# MRF49XA.net
KiCad netlist of a schematic drawn in EAGLE
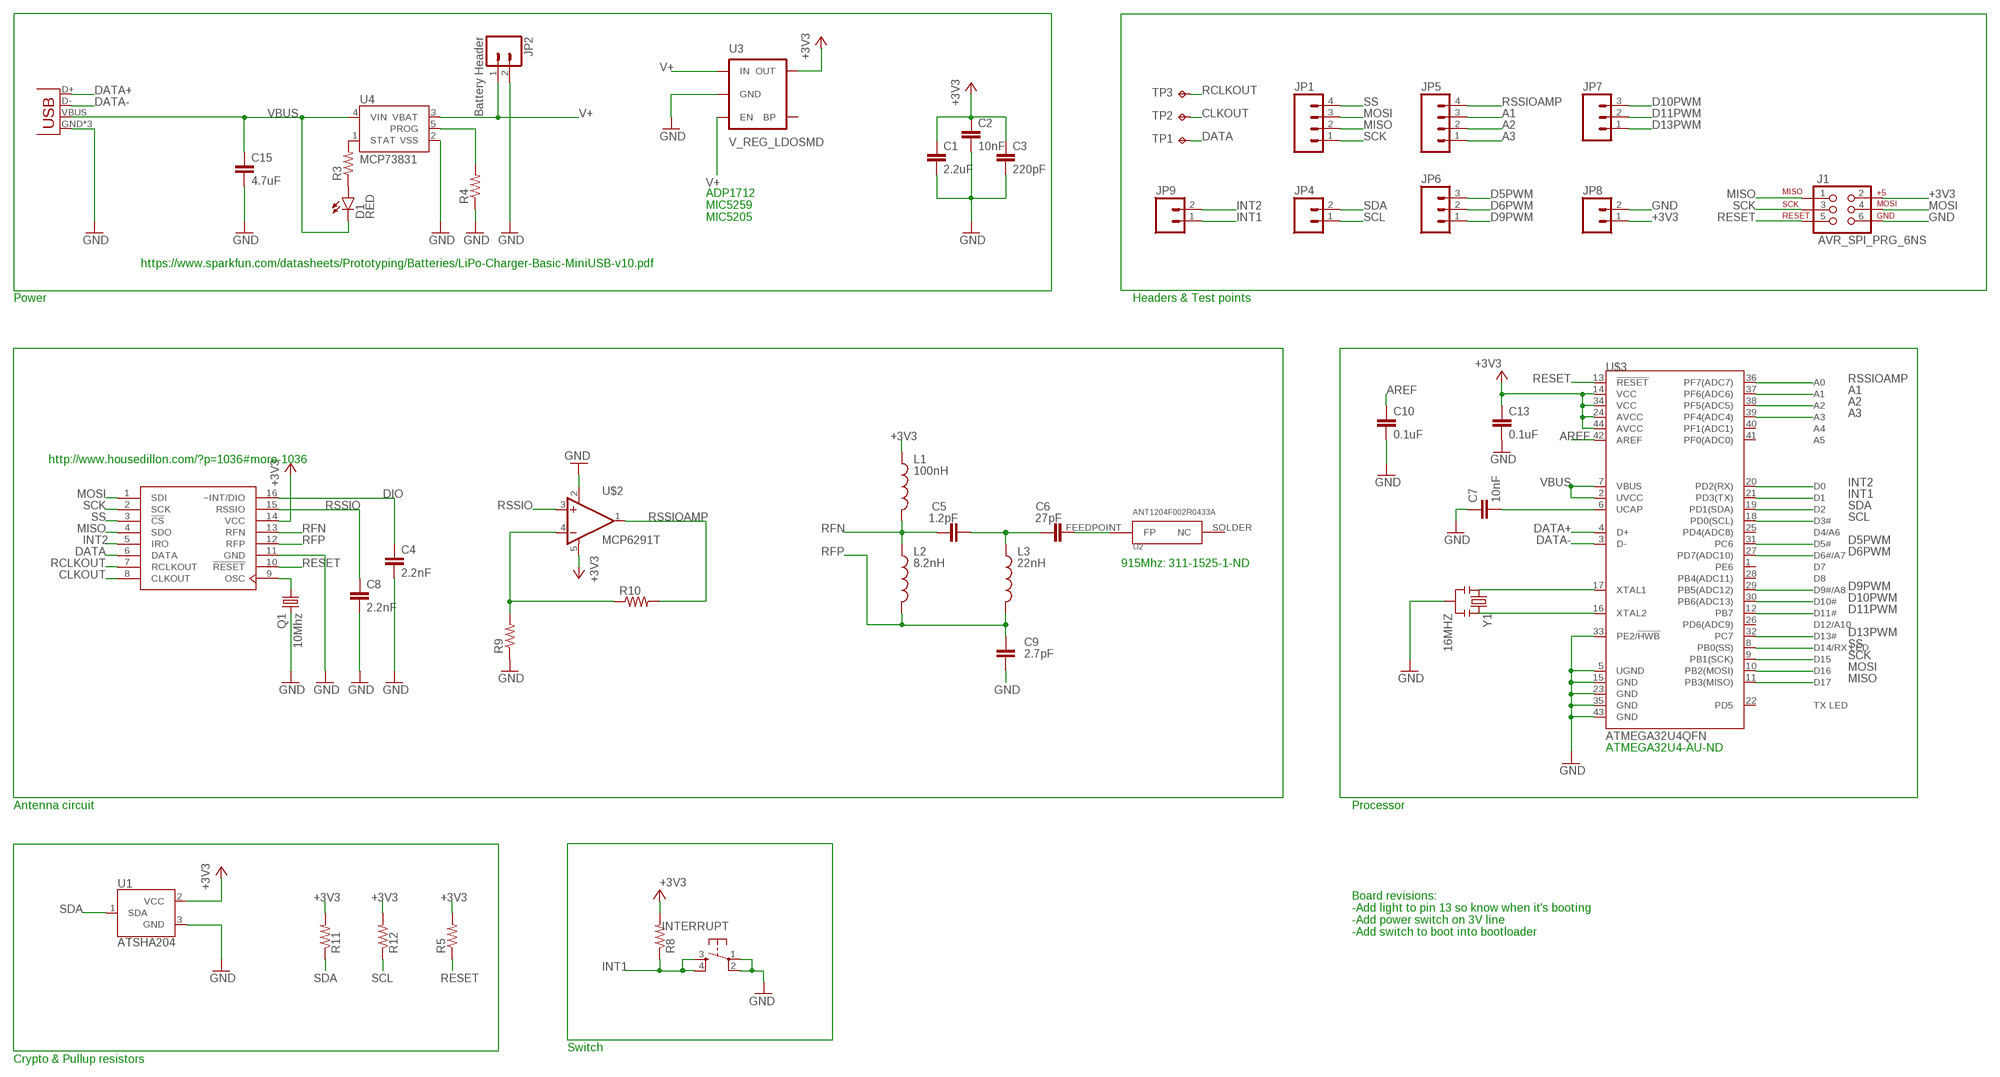
[diagram p0: schematic, sheet 1]

(export (version "E")
  (design (tool "Eeschema 10.0.6"))
  (components
    (comp (ref "C1")
      (value "2.2uF")
      (footprint "eagle-import:0603-CAP")
      (libsource (lib "eagle-import") (part "SparkFun-Passives_CAP0603-CAP"))
    )
    (comp (ref "C2")
      (value "10nF")
      (footprint "eagle-import:0603-CAP")
      (libsource (lib "eagle-import") (part "CAP0603-CAP"))
    )
    (comp (ref "C3")
      (value "220pF")
      (footprint "eagle-import:0603-CAP")
      (libsource (lib "eagle-import") (part "CAP0603-CAP"))
    )
    (comp (ref "C4")
      (value "2.2nF")
      (footprint "eagle-import:0603-CAP")
      (libsource (lib "eagle-import") (part "CAP0603-CAP"))
    )
    (comp (ref "C5")
      (value "1.2pF")
      (footprint "eagle-import:0603-CAP")
      (libsource (lib "eagle-import") (part "SparkFun-Passives_CAP0603-CAP"))
    )
    (comp (ref "C6")
      (value "27pF")
      (footprint "eagle-import:0603-CAP")
      (libsource (lib "eagle-import") (part "SparkFun-Passives_CAP0603-CAP"))
    )
    (comp (ref "C7")
      (value "10nF")
      (footprint "eagle-import:0603-CAP")
      (libsource (lib "eagle-import") (part "CAP0603-CAP"))
    )
    (comp (ref "C8")
      (value "2.2nF")
      (footprint "eagle-import:0603-CAP")
      (libsource (lib "eagle-import") (part "CAP0603-CAP"))
    )
    (comp (ref "C9")
      (value "2.7pF")
      (footprint "eagle-import:0603-CAP")
      (libsource (lib "eagle-import") (part "SparkFun-Passives_CAP0603-CAP"))
    )
    (comp (ref "C10")
      (value "0.1uF")
      (footprint "eagle-import:0603-CAP")
      (libsource (lib "eagle-import") (part "0.1UF-25V-5%(0603)"))
    )
    (comp (ref "C13")
      (value "0.1uF")
      (footprint "eagle-import:0603-CAP")
      (libsource (lib "eagle-import") (part "0.1UF-25V-5%(0603)"))
    )
    (comp (ref "C15")
      (value "4.7uF")
      (footprint "eagle-import:C3216")
      (libsource (lib "eagle-import") (part "C-EUC3216"))
    )
    (comp (ref "D1")
      (value "RED")
      (footprint "eagle-import:LED-0603")
      (libsource (lib "eagle-import") (part "LED-RED0603"))
    )
    (comp (ref "INTERRUPT")
      (value "TAC_SWITCHSMD")
      (footprint "eagle-import:TACTILE-SWITCH-SMD")
      (libsource (lib "eagle-import") (part "TAC_SWITCHSMD"))
    )
    (comp (ref "J1")
      (value "AVR_SPI_PRG_6NS")
      (footprint "eagle-import:2X3-NS")
      (libsource (lib "eagle-import") (part "AVR_SPI_PRG_6NS"))
    )
    (comp (ref "JP1")
      (value "M04PTH")
      (footprint "eagle-import:1X04")
      (libsource (lib "eagle-import") (part "M04PTH"))
    )
    (comp (ref "JP2")
      (value "Battery Header")
      (footprint "eagle-import:1X02_LOCK_LONGPADS")
      (libsource (lib "eagle-import") (part "M02LOCK_LONGPADS"))
    )
    (comp (ref "JP3")
      (value "USB-MICROB")
      (footprint "eagle-import:USB-MICROB")
      (libsource (lib "eagle-import") (part "USB-MICROB"))
    )
    (comp (ref "JP4")
      (value "M02PTH")
      (footprint "eagle-import:1X02")
      (libsource (lib "eagle-import") (part "M02PTH"))
    )
    (comp (ref "JP5")
      (value "M04PTH")
      (footprint "eagle-import:1X04")
      (libsource (lib "eagle-import") (part "M04PTH"))
    )
    (comp (ref "JP6")
      (value "M03PTH")
      (footprint "eagle-import:1X03")
      (libsource (lib "eagle-import") (part "M03PTH"))
    )
    (comp (ref "JP7")
      (value "M03PTH")
      (footprint "eagle-import:1X03")
      (libsource (lib "eagle-import") (part "M03PTH"))
    )
    (comp (ref "JP8")
      (value "M02PTH")
      (footprint "eagle-import:1X02")
      (libsource (lib "eagle-import") (part "M02PTH"))
    )
    (comp (ref "JP9")
      (value "M02PTH")
      (footprint "eagle-import:1X02")
      (libsource (lib "eagle-import") (part "M02PTH"))
    )
    (comp (ref "L1")
      (value "100nH")
      (footprint "eagle-import:0603")
      (libsource (lib "eagle-import") (part "INDUCTOR0603"))
    )
    (comp (ref "L2")
      (value "8.2nH")
      (footprint "eagle-import:0603")
      (libsource (lib "eagle-import") (part "INDUCTOR0603"))
    )
    (comp (ref "L3")
      (value "22nH")
      (footprint "eagle-import:0603")
      (libsource (lib "eagle-import") (part "INDUCTOR0603"))
    )
    (comp (ref "Q1")
      (value "10Mhz")
      (footprint "eagle-import:CTS406")
      (libsource (lib "eagle-import") (part "CRYSTALCTS406"))
    )
    (comp (ref "R3")
      (value "RESISTOR0603-RES")
      (footprint "eagle-import:0603-RES")
      (libsource (lib "eagle-import") (part "RESISTOR0603-RES"))
    )
    (comp (ref "R4")
      (value "R-US_R0603")
      (footprint "eagle-import:R0603")
      (libsource (lib "eagle-import") (part "R-US_R0603"))
    )
    (comp (ref "R5")
      (value "R-US_R0603")
      (footprint "eagle-import:R0603")
      (libsource (lib "eagle-import") (part "R-US_R0603"))
    )
    (comp (ref "R8")
      (value "R-US_R0603")
      (footprint "eagle-import:R0603")
      (libsource (lib "eagle-import") (part "R-US_R0603"))
    )
    (comp (ref "R9")
      (value "R-US_R0603")
      (footprint "eagle-import:R0603")
      (libsource (lib "eagle-import") (part "R-US_R0603"))
    )
    (comp (ref "R10")
      (value "R-US_R0603")
      (footprint "eagle-import:R0603")
      (libsource (lib "eagle-import") (part "R-US_R0603"))
    )
    (comp (ref "R11")
      (value "R-US_R0603")
      (footprint "eagle-import:R0603")
      (libsource (lib "eagle-import") (part "R-US_R0603"))
    )
    (comp (ref "R12")
      (value "R-US_R0603")
      (footprint "eagle-import:R0603")
      (libsource (lib "eagle-import") (part "R-US_R0603"))
    )
    (comp (ref "TP1")
      (value "TPTP08R")
      (footprint "eagle-import:TP08R")
      (libsource (lib "eagle-import") (part "TPTP08R"))
    )
    (comp (ref "TP2")
      (value "TPTP08R")
      (footprint "eagle-import:TP08R")
      (libsource (lib "eagle-import") (part "TPTP08R"))
    )
    (comp (ref "TP3")
      (value "TPTP08R")
      (footprint "eagle-import:TP08R")
      (libsource (lib "eagle-import") (part "TPTP08R"))
    )
    (comp (ref "U$1")
      (value "MRF49XA")
      (footprint "eagle-import:TSSOP16")
      (libsource (lib "eagle-import") (part "MRF49XA"))
    )
    (comp (ref "U$2")
      (value "MCP6291T")
      (footprint "eagle-import:SOT23-5")
      (libsource (lib "eagle-import") (part "MCP6291T-E/OT"))
    )
    (comp (ref "U$3")
      (value "ATMEGA32U4QFN")
      (footprint "eagle-import:QFN-44")
      (libsource (lib "eagle-import") (part "ATMEGA32U4QFN"))
    )
    (comp (ref "U1")
      (value "ATSHA204")
      (footprint "eagle-import:SOT23-3")
      (libsource (lib "eagle-import") (part "ATSHA204-TSU"))
    )
    (comp (ref "U2")
      (value "ANT1204F002R0433A")
      (footprint "eagle-import:ANT1204F002R0433A")
      (libsource (lib "eagle-import") (part "ANT1204F002R0433A"))
    )
    (comp (ref "U3")
      (value "V_REG_LDOSMD")
      (footprint "eagle-import:SOT23-5")
      (libsource (lib "eagle-import") (part "V_REG_LDOSMD"))
    )
    (comp (ref "U4")
      (value "MCP73831")
      (footprint "eagle-import:SOT23-5")
      (libsource (lib "eagle-import") (part "MCP73831"))
    )
    (comp (ref "Y1")
      (value "16MHZ")
      (footprint "eagle-import:RESONATOR-SMD")
      (libsource (lib "eagle-import") (part "RESONATOR8MHZ"))
    )
  )
  (nets
    (net (code "1") (name "+3V3") (class "Default")
      (node (ref "C1") (pin "1") (pinfunction "1_1") (pintype "passive"))
      (node (ref "C13") (pin "1") (pinfunction "1_1") (pintype "passive"))
      (node (ref "C2") (pin "1") (pinfunction "1_1") (pintype "passive"))
      (node (ref "C3") (pin "1") (pinfunction "1_1") (pintype "passive"))
      (node (ref "J1") (pin "2") (pinfunction "2_2") (pintype "passive"))
      (node (ref "JP8") (pin "1") (pinfunction "1_1") (pintype "passive"))
      (node (ref "L1") (pin "1") (pinfunction "1_1") (pintype "passive"))
      (node (ref "R11") (pin "2") (pinfunction "2_2") (pintype "passive"))
      (node (ref "R12") (pin "2") (pinfunction "2_2") (pintype "passive"))
      (node (ref "R5") (pin "2") (pinfunction "2_2") (pintype "passive"))
      (node (ref "R8") (pin "2") (pinfunction "2_2") (pintype "passive"))
      (node (ref "U$1") (pin "14") (pinfunction "VCC_14") (pintype "bidirectional"))
      (node (ref "U$2") (pin "5") (pinfunction "V+_5") (pintype "power_in"))
      (node (ref "U$3") (pin "14") (pinfunction "VCC_14") (pintype "bidirectional"))
      (node (ref "U$3") (pin "24") (pinfunction "AVCC_24") (pintype "bidirectional"))
      (node (ref "U$3") (pin "34") (pinfunction "VCC_34") (pintype "bidirectional"))
      (node (ref "U$3") (pin "44") (pinfunction "AVCC_44") (pintype "bidirectional"))
      (node (ref "U1") (pin "2") (pinfunction "VCC_2") (pintype "bidirectional"))
      (node (ref "U3") (pin "5") (pinfunction "OUT_5") (pintype "passive"))
    )
    (net (code "2") (name "/A1") (class "Default")
      (node (ref "JP5") (pin "3") (pinfunction "3_3") (pintype "passive"))
      (node (ref "U$3") (pin "37") (pinfunction "PF6(ADC6)_37") (pintype "bidirectional"))
    )
    (net (code "3") (name "/A2") (class "Default")
      (node (ref "JP5") (pin "2") (pinfunction "2_2") (pintype "passive"))
      (node (ref "U$3") (pin "38") (pinfunction "PF5(ADC5)_38") (pintype "bidirectional"))
    )
    (net (code "4") (name "/A3") (class "Default")
      (node (ref "JP5") (pin "1") (pinfunction "1_1") (pintype "passive"))
      (node (ref "U$3") (pin "39") (pinfunction "PF4(ADC4)_39") (pintype "bidirectional"))
    )
    (net (code "5") (name "/AREF") (class "Default")
      (node (ref "C10") (pin "1") (pinfunction "1_1") (pintype "passive"))
      (node (ref "U$3") (pin "42") (pinfunction "AREF_42") (pintype "bidirectional"))
    )
    (net (code "6") (name "/CLKOUT") (class "Default")
      (node (ref "TP2") (pin "TP") (pinfunction "TP_TP") (pintype "input"))
      (node (ref "U$1") (pin "8") (pinfunction "CLKOUT_8") (pintype "output"))
    )
    (net (code "7") (name "/D5PWM") (class "Default")
      (node (ref "JP6") (pin "3") (pinfunction "3_3") (pintype "passive"))
      (node (ref "U$3") (pin "31") (pinfunction "PC6_31") (pintype "bidirectional"))
    )
    (net (code "8") (name "/D6PWM") (class "Default")
      (node (ref "JP6") (pin "2") (pinfunction "2_2") (pintype "passive"))
      (node (ref "U$3") (pin "27") (pinfunction "PD7(ADC10)_27") (pintype "bidirectional"))
    )
    (net (code "9") (name "/D9PWM") (class "Default")
      (node (ref "JP6") (pin "1") (pinfunction "1_1") (pintype "passive"))
      (node (ref "U$3") (pin "29") (pinfunction "PB5(ADC12)_29") (pintype "bidirectional"))
    )
    (net (code "10") (name "/D10PWM") (class "Default")
      (node (ref "JP7") (pin "3") (pinfunction "3_3") (pintype "passive"))
      (node (ref "U$3") (pin "30") (pinfunction "PB6(ADC13)_30") (pintype "bidirectional"))
    )
    (net (code "11") (name "/D11PWM") (class "Default")
      (node (ref "JP7") (pin "2") (pinfunction "2_2") (pintype "passive"))
      (node (ref "U$3") (pin "12") (pinfunction "PB7_12") (pintype "bidirectional"))
    )
    (net (code "12") (name "/D13PWM") (class "Default")
      (node (ref "JP7") (pin "1") (pinfunction "1_1") (pintype "passive"))
      (node (ref "U$3") (pin "32") (pinfunction "PC7_32") (pintype "bidirectional"))
    )
    (net (code "13") (name "/DATA") (class "Default")
      (node (ref "TP1") (pin "TP") (pinfunction "TP_TP") (pintype "input"))
      (node (ref "U$1") (pin "6") (pinfunction "DATA_6") (pintype "bidirectional"))
    )
    (net (code "14") (name "/DATA+") (class "Default")
      (node (ref "JP3") (pin "D+") (pinfunction "D+_D+") (pintype "bidirectional"))
      (node (ref "U$3") (pin "4") (pinfunction "D+_4") (pintype "bidirectional"))
    )
    (net (code "15") (name "/DATA-") (class "Default")
      (node (ref "JP3") (pin "D-") (pinfunction "D-_D-") (pintype "bidirectional"))
      (node (ref "U$3") (pin "3") (pinfunction "D-_3") (pintype "bidirectional"))
    )
    (net (code "16") (name "/DIO") (class "Default")
      (node (ref "C4") (pin "1") (pinfunction "1_1") (pintype "passive"))
      (node (ref "U$1") (pin "16") (pinfunction "~{INT/DIO}_16") (pintype "bidirectional"))
    )
    (net (code "17") (name "/INT1") (class "Default")
      (node (ref "INTERRUPT") (pin "3") (pinfunction "3_3") (pintype "passive"))
      (node (ref "INTERRUPT") (pin "4") (pinfunction "4_4") (pintype "passive"))
      (node (ref "JP9") (pin "1") (pinfunction "1_1") (pintype "passive"))
      (node (ref "R8") (pin "1") (pinfunction "1_1") (pintype "passive"))
      (node (ref "U$3") (pin "21") (pinfunction "PD3(TX)_21") (pintype "bidirectional"))
    )
    (net (code "18") (name "/INT2") (class "Default")
      (node (ref "JP9") (pin "2") (pinfunction "2_2") (pintype "passive"))
      (node (ref "U$1") (pin "5") (pinfunction "IRO_5") (pintype "output"))
      (node (ref "U$3") (pin "20") (pinfunction "PD2(RX)_20") (pintype "bidirectional"))
    )
    (net (code "19") (name "/MISO") (class "Default")
      (node (ref "J1") (pin "1") (pinfunction "1_1") (pintype "passive"))
      (node (ref "JP1") (pin "2") (pinfunction "2_2") (pintype "passive"))
      (node (ref "U$1") (pin "4") (pinfunction "SDO_4") (pintype "output"))
      (node (ref "U$3") (pin "11") (pinfunction "PB3(MISO)_11") (pintype "bidirectional"))
    )
    (net (code "20") (name "/MOSI") (class "Default")
      (node (ref "J1") (pin "4") (pinfunction "4_4") (pintype "passive"))
      (node (ref "JP1") (pin "3") (pinfunction "3_3") (pintype "passive"))
      (node (ref "U$1") (pin "1") (pinfunction "SDI_1") (pintype "input"))
      (node (ref "U$3") (pin "10") (pinfunction "PB2(MOSI)_10") (pintype "bidirectional"))
    )
    (net (code "21") (name "/RCLKOUT") (class "Default")
      (node (ref "TP3") (pin "TP") (pinfunction "TP_TP") (pintype "input"))
      (node (ref "U$1") (pin "7") (pinfunction "RCLKOUT_7") (pintype "bidirectional"))
    )
    (net (code "22") (name "/RESET") (class "Default")
      (node (ref "J1") (pin "5") (pinfunction "5_5") (pintype "passive"))
      (node (ref "R5") (pin "1") (pinfunction "1_1") (pintype "passive"))
      (node (ref "U$1") (pin "10") (pinfunction "~{RESET}_10") (pintype "bidirectional"))
      (node (ref "U$3") (pin "13") (pinfunction "~{RESET}_13") (pintype "bidirectional"))
    )
    (net (code "23") (name "/RFN") (class "Default")
      (node (ref "C5") (pin "1") (pinfunction "1_1") (pintype "passive"))
      (node (ref "L1") (pin "2") (pinfunction "2_2") (pintype "passive"))
      (node (ref "L2") (pin "1") (pinfunction "1_1") (pintype "passive"))
      (node (ref "U$1") (pin "13") (pinfunction "RFN_13") (pintype "bidirectional"))
    )
    (net (code "24") (name "/RFP") (class "Default")
      (node (ref "C9") (pin "1") (pinfunction "1_1") (pintype "passive"))
      (node (ref "L2") (pin "2") (pinfunction "2_2") (pintype "passive"))
      (node (ref "L3") (pin "2") (pinfunction "2_2") (pintype "passive"))
      (node (ref "U$1") (pin "12") (pinfunction "RFP_12") (pintype "bidirectional"))
    )
    (net (code "25") (name "/RSSIO") (class "Default")
      (node (ref "C8") (pin "1") (pinfunction "1_1") (pintype "passive"))
      (node (ref "U$1") (pin "15") (pinfunction "RSSIO_15") (pintype "bidirectional"))
      (node (ref "U$2") (pin "3") (pinfunction "+IN_3") (pintype "input"))
    )
    (net (code "26") (name "/RSSIOAMP") (class "Default")
      (node (ref "JP5") (pin "4") (pinfunction "4_4") (pintype "passive"))
      (node (ref "R10") (pin "2") (pinfunction "2_2") (pintype "passive"))
      (node (ref "U$2") (pin "1") (pinfunction "OUT_1") (pintype "output"))
      (node (ref "U$3") (pin "36") (pinfunction "PF7(ADC7)_36") (pintype "bidirectional"))
    )
    (net (code "27") (name "/SCK") (class "Default")
      (node (ref "J1") (pin "3") (pinfunction "3_3") (pintype "passive"))
      (node (ref "JP1") (pin "1") (pinfunction "1_1") (pintype "passive"))
      (node (ref "U$1") (pin "2") (pinfunction "SCK_2") (pintype "input"))
      (node (ref "U$3") (pin "9") (pinfunction "PB1(SCK)_9") (pintype "bidirectional"))
    )
    (net (code "28") (name "/SCL") (class "Default")
      (node (ref "JP4") (pin "1") (pinfunction "1_1") (pintype "passive"))
      (node (ref "R12") (pin "1") (pinfunction "1_1") (pintype "passive"))
      (node (ref "U$3") (pin "18") (pinfunction "PD0(SCL)_18") (pintype "bidirectional"))
    )
    (net (code "29") (name "/SDA") (class "Default")
      (node (ref "JP4") (pin "2") (pinfunction "2_2") (pintype "passive"))
      (node (ref "R11") (pin "1") (pinfunction "1_1") (pintype "passive"))
      (node (ref "U$3") (pin "19") (pinfunction "PD1(SDA)_19") (pintype "bidirectional"))
      (node (ref "U1") (pin "1") (pinfunction "SDA_1") (pintype "bidirectional"))
    )
    (net (code "30") (name "/SS") (class "Default")
      (node (ref "JP1") (pin "4") (pinfunction "4_4") (pintype "passive"))
      (node (ref "U$1") (pin "3") (pinfunction "~{CS}_3") (pintype "input"))
      (node (ref "U$3") (pin "8") (pinfunction "PB0(SS)_8") (pintype "bidirectional"))
    )
    (net (code "31") (name "/V+") (class "Default")
      (node (ref "JP2") (pin "1") (pinfunction "1_1") (pintype "passive"))
      (node (ref "U3") (pin "1") (pinfunction "IN_1") (pintype "input"))
      (node (ref "U3") (pin "3") (pinfunction "EN_3") (pintype "input"))
      (node (ref "U4") (pin "3") (pinfunction "VBAT_3") (pintype "power_in"))
    )
    (net (code "32") (name "/VBUS") (class "Default")
      (node (ref "C15") (pin "1") (pinfunction "1_1") (pintype "passive"))
      (node (ref "D1") (pin "C") (pinfunction "C_C") (pintype "passive"))
      (node (ref "JP3") (pin "VBUS") (pinfunction "VBUS_VBUS") (pintype "bidirectional"))
      (node (ref "U$3") (pin "2") (pinfunction "UVCC_2") (pintype "bidirectional"))
      (node (ref "U$3") (pin "7") (pinfunction "VBUS_7") (pintype "bidirectional"))
      (node (ref "U4") (pin "4") (pinfunction "VIN_4") (pintype "power_in"))
    )
    (net (code "33") (name "GND") (class "Default")
      (node (ref "C1") (pin "2") (pinfunction "2_2") (pintype "passive"))
      (node (ref "C10") (pin "2") (pinfunction "2_2") (pintype "passive"))
      (node (ref "C13") (pin "2") (pinfunction "2_2") (pintype "passive"))
      (node (ref "C15") (pin "2") (pinfunction "2_2") (pintype "passive"))
      (node (ref "C2") (pin "2") (pinfunction "2_2") (pintype "passive"))
      (node (ref "C3") (pin "2") (pinfunction "2_2") (pintype "passive"))
      (node (ref "C4") (pin "2") (pinfunction "2_2") (pintype "passive"))
      (node (ref "C7") (pin "1") (pinfunction "1_1") (pintype "passive"))
      (node (ref "C8") (pin "2") (pinfunction "2_2") (pintype "passive"))
      (node (ref "C9") (pin "2") (pinfunction "2_2") (pintype "passive"))
      (node (ref "INTERRUPT") (pin "1") (pinfunction "1_1") (pintype "passive"))
      (node (ref "INTERRUPT") (pin "2") (pinfunction "2_2") (pintype "passive"))
      (node (ref "J1") (pin "6") (pinfunction "6_6") (pintype "passive"))
      (node (ref "JP2") (pin "2") (pinfunction "2_2") (pintype "passive"))
      (node (ref "JP3") (pin "GND") (pinfunction "GND_GND") (pintype "bidirectional"))
      (node (ref "JP3") (pin "MT1") (pinfunction "GND_MT1") (pintype "bidirectional"))
      (node (ref "JP3") (pin "MT2") (pinfunction "GND_MT2") (pintype "bidirectional"))
      (node (ref "JP8") (pin "2") (pinfunction "2_2") (pintype "passive"))
      (node (ref "Q1") (pin "3") (pinfunction "2_3") (pintype "passive"))
      (node (ref "R4") (pin "1") (pinfunction "1_1") (pintype "passive"))
      (node (ref "R9") (pin "1") (pinfunction "1_1") (pintype "passive"))
      (node (ref "U$1") (pin "11") (pinfunction "GND_11") (pintype "bidirectional"))
      (node (ref "U$2") (pin "2") (pinfunction "V-_2") (pintype "power_in"))
      (node (ref "U$3") (pin "15") (pinfunction "GND_15") (pintype "bidirectional"))
      (node (ref "U$3") (pin "23") (pinfunction "GND_23") (pintype "bidirectional"))
      (node (ref "U$3") (pin "33") (pinfunction "PE2/~{HWB}_33") (pintype "bidirectional"))
      (node (ref "U$3") (pin "35") (pinfunction "GND_35") (pintype "bidirectional"))
      (node (ref "U$3") (pin "43") (pinfunction "GND_43") (pintype "bidirectional"))
      (node (ref "U$3") (pin "5") (pinfunction "UGND_5") (pintype "bidirectional"))
      (node (ref "U1") (pin "3") (pinfunction "GND_3") (pintype "bidirectional"))
      (node (ref "U3") (pin "2") (pinfunction "GND_2") (pintype "input"))
      (node (ref "U4") (pin "2") (pinfunction "VSS_2") (pintype "power_in"))
      (node (ref "Y1") (pin "2") (pinfunction "2_2") (pintype "passive"))
    )
    (net (code "34") (name "Net-(C5-Pad2)") (class "Default")
      (node (ref "C5") (pin "2") (pinfunction "2_2") (pintype "passive"))
      (node (ref "C6") (pin "1") (pinfunction "1_1") (pintype "passive"))
      (node (ref "L3") (pin "1") (pinfunction "1_1") (pintype "passive"))
    )
    (net (code "35") (name "Net-(D1-PadA)") (class "Default")
      (node (ref "D1") (pin "A") (pinfunction "A_A") (pintype "passive"))
      (node (ref "R3") (pin "1") (pinfunction "1_1") (pintype "passive"))
    )
    (net (code "36") (name "Net-(U$1A-OSC)") (class "Default")
      (node (ref "Q1") (pin "1") (pinfunction "1_1") (pintype "passive"))
      (node (ref "U$1") (pin "9") (pinfunction "OSC_9") (pintype "bidirectional"))
    )
    (net (code "37") (name "Net-(U$2--IN)") (class "Default")
      (node (ref "R10") (pin "1") (pinfunction "1_1") (pintype "passive"))
      (node (ref "R9") (pin "2") (pinfunction "2_2") (pintype "passive"))
      (node (ref "U$2") (pin "4") (pinfunction "-IN_4") (pintype "input"))
    )
    (net (code "38") (name "Net-(U$3-UCAP)") (class "Default")
      (node (ref "C7") (pin "2") (pinfunction "2_2") (pintype "passive"))
      (node (ref "U$3") (pin "6") (pinfunction "UCAP_6") (pintype "bidirectional"))
    )
    (net (code "39") (name "Net-(U$3-XTAL1)") (class "Default")
      (node (ref "U$3") (pin "17") (pinfunction "XTAL1_17") (pintype "bidirectional"))
      (node (ref "Y1") (pin "1") (pinfunction "1_1") (pintype "passive"))
    )
    (net (code "40") (name "Net-(U$3-XTAL2)") (class "Default")
      (node (ref "U$3") (pin "16") (pinfunction "XTAL2_16") (pintype "bidirectional"))
      (node (ref "Y1") (pin "3") (pinfunction "3_3") (pintype "passive"))
    )
    (net (code "41") (name "Net-(U2-FP)") (class "Default")
      (node (ref "C6") (pin "2") (pinfunction "2_2") (pintype "passive"))
      (node (ref "U2") (pin "FEEDPOINT") (pinfunction "FP_FEEDPOINT") (pintype "bidirectional"))
    )
    (net (code "42") (name "Net-(U4-PROG)") (class "Default")
      (node (ref "R4") (pin "2") (pinfunction "2_2") (pintype "passive"))
      (node (ref "U4") (pin "5") (pinfunction "PROG_5") (pintype "input"))
    )
    (net (code "43") (name "Net-(U4-STAT)") (class "Default")
      (node (ref "R3") (pin "2") (pinfunction "2_2") (pintype "passive"))
      (node (ref "U4") (pin "1") (pinfunction "STAT_1") (pintype "output"))
    )
    (net (code "44") (name "unconnected-(U$3-PB4(ADC11)-Pad28)") (class "Default")
      (node (ref "U$3") (pin "28") (pinfunction "PB4(ADC11)_28") (pintype "bidirectional"))
    )
    (net (code "45") (name "unconnected-(U$3-PD4(ADC8)-Pad25)") (class "Default")
      (node (ref "U$3") (pin "25") (pinfunction "PD4(ADC8)_25") (pintype "bidirectional"))
    )
    (net (code "46") (name "unconnected-(U$3-PD5-Pad22)") (class "Default")
      (node (ref "U$3") (pin "22") (pinfunction "PD5_22") (pintype "bidirectional"))
    )
    (net (code "47") (name "unconnected-(U$3-PD6(ADC9)-Pad26)") (class "Default")
      (node (ref "U$3") (pin "26") (pinfunction "PD6(ADC9)_26") (pintype "bidirectional"))
    )
    (net (code "48") (name "unconnected-(U$3-PE6-Pad1)") (class "Default")
      (node (ref "U$3") (pin "1") (pinfunction "PE6_1") (pintype "bidirectional"))
    )
    (net (code "49") (name "unconnected-(U$3-PF0(ADC0)-Pad41)") (class "Default")
      (node (ref "U$3") (pin "41") (pinfunction "PF0(ADC0)_41") (pintype "bidirectional"))
    )
    (net (code "50") (name "unconnected-(U$3-PF1(ADC1)-Pad40)") (class "Default")
      (node (ref "U$3") (pin "40") (pinfunction "PF1(ADC1)_40") (pintype "bidirectional"))
    )
    (net (code "51") (name "unconnected-(U2-NC-PadSOLDER)") (class "Default")
      (node (ref "U2") (pin "SOLDER") (pinfunction "NC_SOLDER") (pintype "no_connect"))
    )
    (net (code "52") (name "unconnected-(U3-BP-Pad4)") (class "Default")
      (node (ref "U3") (pin "4") (pinfunction "BP_4") (pintype "input"))
    )
  )
)
